# SLOPE_Undergraduate_Student_Instrumentat.net
KiCad netlist of a schematic drawn in EAGLE
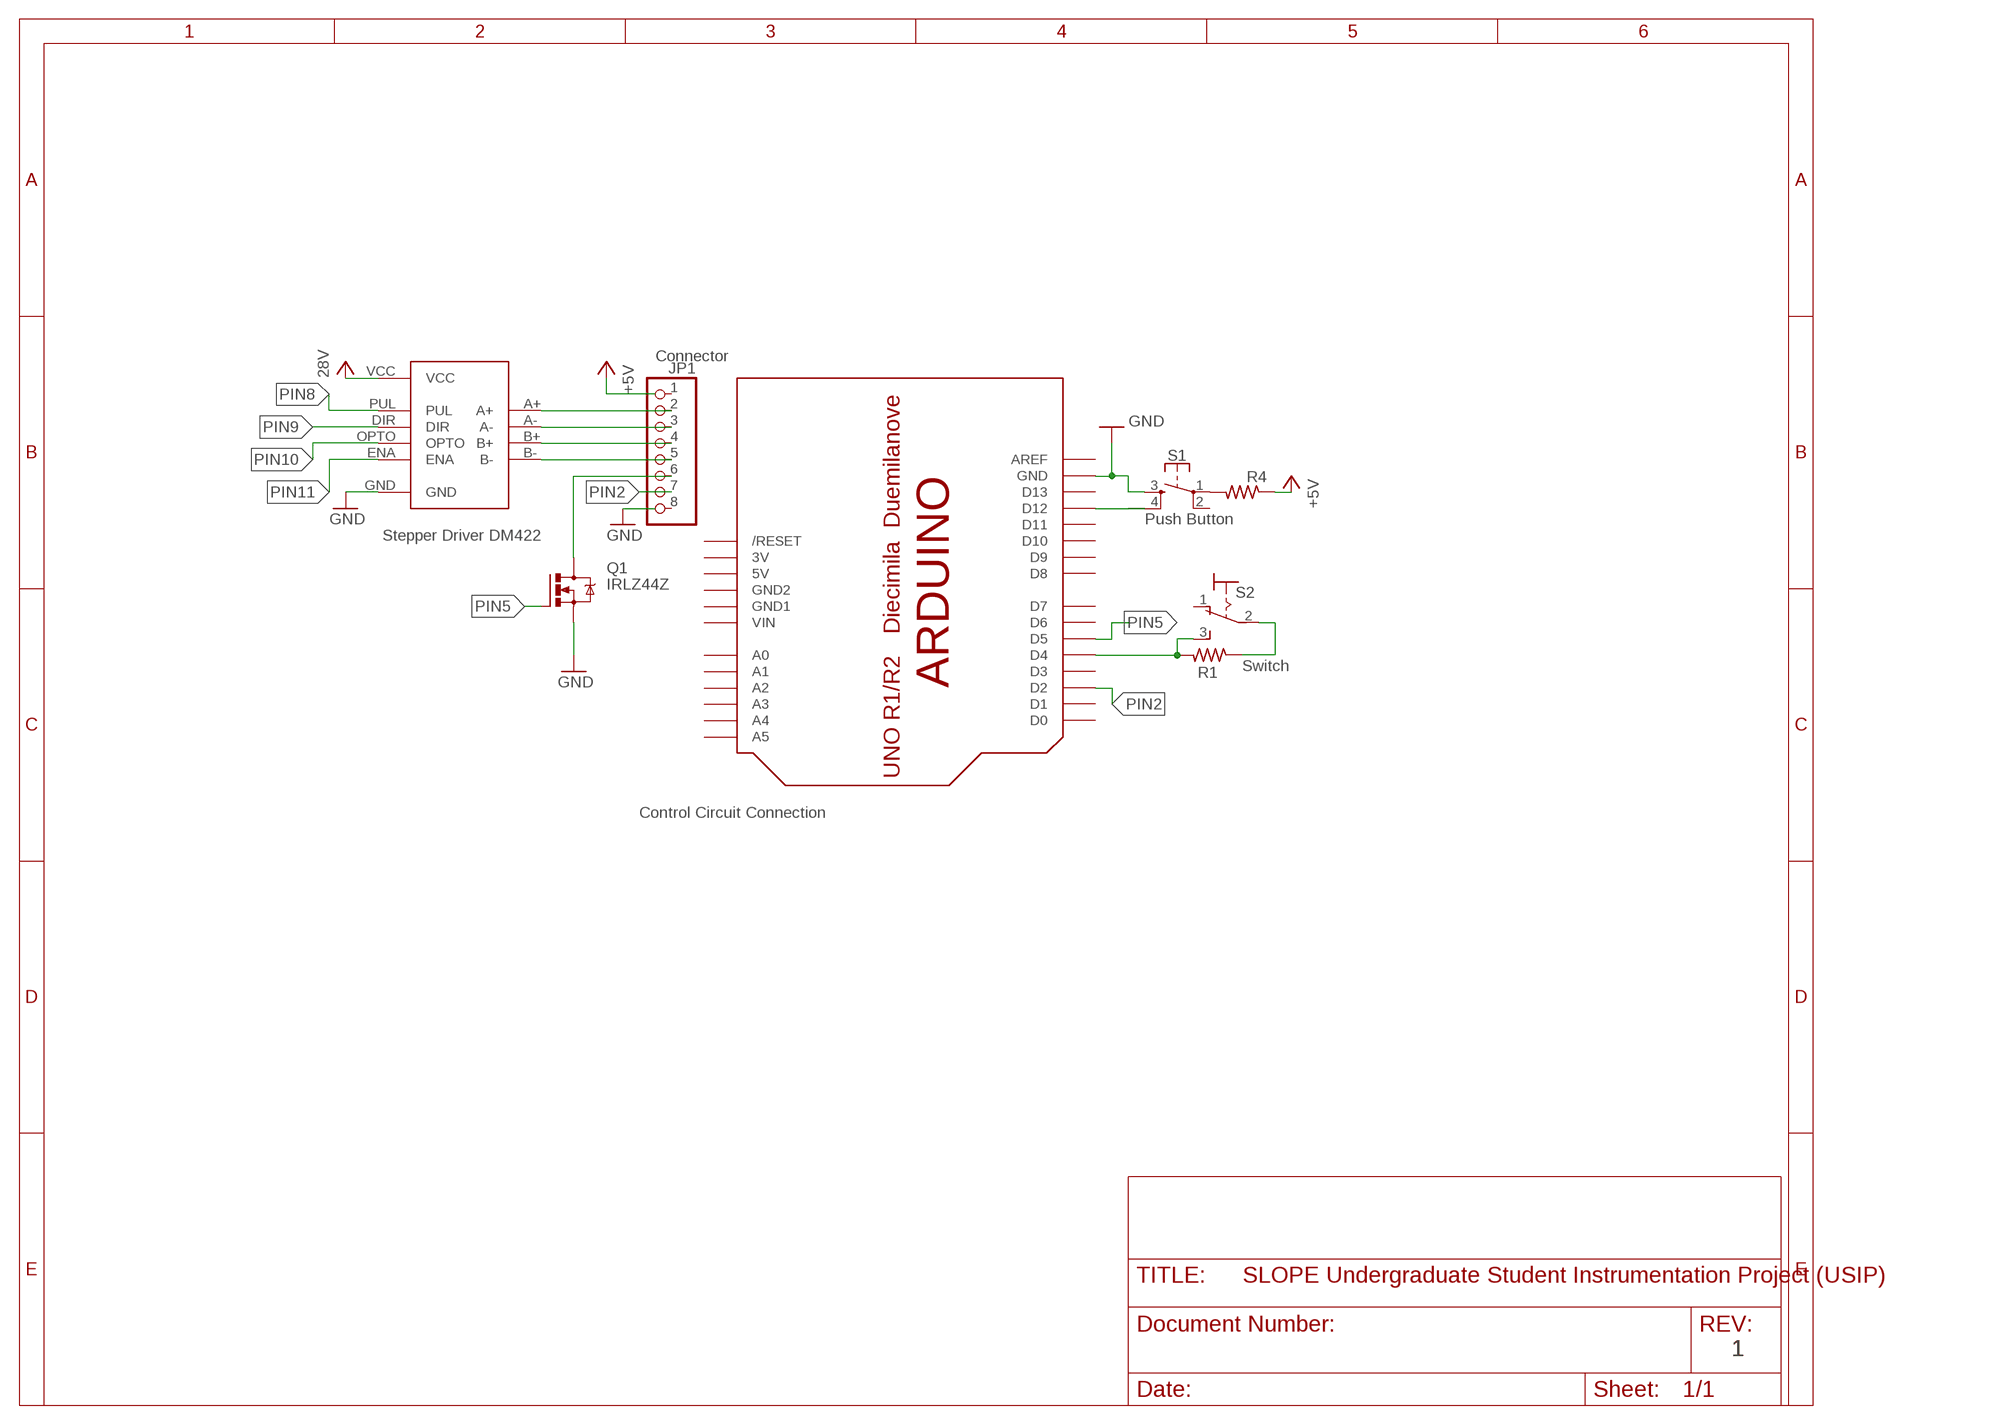
[diagram p0: schematic, sheet 1]

(export (version "E")
  (design (tool "Eeschema 10.0.6"))
  (components
    (comp (ref "JP1")
      (value "PINHD-1X8")
      (footprint "eagle-import:1X08")
      (libsource (lib "eagle-import") (part "PINHD-1X8"))
    )
    (comp (ref "Q1")
      (value "IRLZ44Z")
      (footprint "eagle-import:TO220BH")
      (libsource (lib "eagle-import") (part "IRLZ44Z"))
    )
    (comp (ref "R1")
      (value "R-US_0204/5")
      (footprint "eagle-import:0204_5")
      (libsource (lib "eagle-import") (part "R-US_0204/5"))
    )
    (comp (ref "R4")
      (value "R-US_0204/5")
      (footprint "eagle-import:0204_5")
      (libsource (lib "eagle-import") (part "R-US_0204/5"))
    )
    (comp (ref "S1")
      (value "MOMENTARY-SWITCH-SPST-2-SMD-5.2MM")
      (footprint "eagle-import:TACTILE_SWITCH_SMD_5.2MM")
      (libsource (lib "eagle-import") (part "MOMENTARY-SWITCH-SPST-2-SMD-5.2MM"))
    )
    (comp (ref "S2")
      (value "320-916")
      (footprint "eagle-import:320-916")
      (libsource (lib "eagle-import") (part "320-916"))
    )
    (comp (ref "U$1")
      (value "ARDUINO-BPLACE")
      (footprint "eagle-import:ARDUINO-BPLACE")
      (libsource (lib "eagle-import") (part "ARDUINO-BPLACE"))
    )
    (comp (ref "U$2")
      (value "DM422")
      (footprint "eagle-import:DIL14")
      (libsource (lib "eagle-import") (part "DM422"))
    )
  )
  (nets
    (net (code "1") (name "+5V") (class "Default")
      (node (ref "R4") (pin "1") (pinfunction "1_1") (pintype "passive"))
    )
    (net (code "2") (name "/3V") (class "Default")
      (node (ref "U$1") (pin "3V") (pinfunction "3V_3V") (pintype "power_in"))
    )
    (net (code "3") (name "/5V") (class "Default")
      (node (ref "U$1") (pin "5V") (pinfunction "5V_5V") (pintype "power_in"))
    )
    (net (code "4") (name "/GND1") (class "Default")
      (node (ref "U$1") (pin "GND1") (pinfunction "GND1_GND1") (pintype "power_in"))
    )
    (net (code "5") (name "/GND2") (class "Default")
      (node (ref "U$1") (pin "GND2") (pinfunction "GND2_GND2") (pintype "power_in"))
    )
    (net (code "6") (name "/VIN") (class "Default")
      (node (ref "U$1") (pin "VIN") (pinfunction "VIN_VIN") (pintype "power_in"))
    )
    (net (code "7") (name "28V") (class "Default")
      (node (ref "U$2") (pin "VCC") (pinfunction "VCC_VCC") (pintype "power_in"))
    )
    (net (code "8") (name "GND") (class "Default")
      (node (ref "Q1") (pin "S") (pinfunction "S_S") (pintype "passive"))
      (node (ref "S1") (pin "3") (pinfunction "3_3") (pintype "passive"))
      (node (ref "U$1") (pin "GND") (pinfunction "GND_GND") (pintype "power_in"))
      (node (ref "U$2") (pin "GND") (pinfunction "GND_GND") (pintype "power_in"))
    )
    (net (code "9") (name "Net-(JP1-Pad2)") (class "Default")
      (node (ref "JP1") (pin "2") (pinfunction "2_2") (pintype "passive"))
      (node (ref "U$2") (pin "A+") (pinfunction "A+_A+") (pintype "output"))
    )
    (net (code "10") (name "Net-(JP1-Pad3)") (class "Default")
      (node (ref "JP1") (pin "3") (pinfunction "3_3") (pintype "passive"))
      (node (ref "U$2") (pin "A-") (pinfunction "A-_A-") (pintype "output"))
    )
    (net (code "11") (name "Net-(JP1-Pad4)") (class "Default")
      (node (ref "JP1") (pin "4") (pinfunction "4_4") (pintype "passive"))
      (node (ref "U$2") (pin "B+") (pinfunction "B+_B+") (pintype "output"))
    )
    (net (code "12") (name "Net-(JP1-Pad5)") (class "Default")
      (node (ref "JP1") (pin "5") (pinfunction "5_5") (pintype "passive"))
      (node (ref "U$2") (pin "B-") (pinfunction "B-_B-") (pintype "output"))
    )
    (net (code "13") (name "Net-(JP1-Pad6)") (class "Default")
      (node (ref "JP1") (pin "6") (pinfunction "6_6") (pintype "passive"))
      (node (ref "Q1") (pin "D") (pinfunction "D_D") (pintype "passive"))
    )
    (net (code "14") (name "Net-(R4-Pad2)") (class "Default")
      (node (ref "R4") (pin "2") (pinfunction "2_2") (pintype "passive"))
      (node (ref "S1") (pin "1") (pinfunction "1_1") (pintype "passive"))
    )
    (net (code "15") (name "Net-(S1-Pad4)") (class "Default")
      (node (ref "S1") (pin "4") (pinfunction "4_4") (pintype "passive"))
      (node (ref "U$1") (pin "D12") (pinfunction "D12_D12") (pintype "bidirectional"))
    )
    (net (code "16") (name "Net-(S2-P)") (class "Default")
      (node (ref "R1") (pin "1") (pinfunction "1_1") (pintype "passive"))
      (node (ref "S2") (pin "2") (pinfunction "P_2") (pintype "passive"))
    )
    (net (code "17") (name "Net-(S2-S)") (class "Default")
      (node (ref "R1") (pin "2") (pinfunction "2_2") (pintype "passive"))
      (node (ref "S2") (pin "3") (pinfunction "S_3") (pintype "passive"))
      (node (ref "U$1") (pin "D4") (pinfunction "D4_D4") (pintype "bidirectional"))
    )
    (net (code "18") (name "PIN2") (class "Default")
      (node (ref "JP1") (pin "7") (pinfunction "7_7") (pintype "passive"))
      (node (ref "U$1") (pin "D2") (pinfunction "D2_D2") (pintype "bidirectional"))
    )
    (net (code "19") (name "PIN5") (class "Default")
      (node (ref "Q1") (pin "G") (pinfunction "G_G") (pintype "passive"))
      (node (ref "U$1") (pin "D5") (pinfunction "D5_D5") (pintype "bidirectional"))
    )
    (net (code "20") (name "PIN8") (class "Default")
      (node (ref "U$2") (pin "PUL") (pinfunction "PUL_PUL") (pintype "bidirectional"))
    )
    (net (code "21") (name "PIN9") (class "Default")
      (node (ref "U$2") (pin "DIR") (pinfunction "DIR_DIR") (pintype "bidirectional"))
    )
    (net (code "22") (name "PIN10") (class "Default")
      (node (ref "U$2") (pin "OPTO") (pinfunction "OPTO_OPTO") (pintype "bidirectional"))
    )
    (net (code "23") (name "PIN11") (class "Default")
      (node (ref "U$2") (pin "ENA") (pinfunction "ENA_ENA") (pintype "bidirectional"))
    )
    (net (code "24") (name "unconnected-(JP1-Pad1)") (class "Default")
      (node (ref "JP1") (pin "1") (pinfunction "1_1") (pintype "passive"))
    )
    (net (code "25") (name "unconnected-(JP1-Pad8)") (class "Default")
      (node (ref "JP1") (pin "8") (pinfunction "8_8") (pintype "passive"))
    )
    (net (code "26") (name "unconnected-(S1-Pad2)") (class "Default")
      (node (ref "S1") (pin "2") (pinfunction "2_2") (pintype "passive"))
    )
    (net (code "27") (name "unconnected-(S2-O-Pad1)") (class "Default")
      (node (ref "S2") (pin "1") (pinfunction "O_1") (pintype "passive"))
    )
    (net (code "28") (name "unconnected-(U$1-PadA0)") (class "Default")
      (node (ref "U$1") (pin "A0") (pinfunction "A0_A0") (pintype "bidirectional"))
    )
    (net (code "29") (name "unconnected-(U$1-PadA1)") (class "Default")
      (node (ref "U$1") (pin "A1") (pinfunction "A1_A1") (pintype "bidirectional"))
    )
    (net (code "30") (name "unconnected-(U$1-PadA2)") (class "Default")
      (node (ref "U$1") (pin "A2") (pinfunction "A2_A2") (pintype "bidirectional"))
    )
    (net (code "31") (name "unconnected-(U$1-PadA3)") (class "Default")
      (node (ref "U$1") (pin "A3") (pinfunction "A3_A3") (pintype "bidirectional"))
    )
    (net (code "32") (name "unconnected-(U$1-PadA4)") (class "Default")
      (node (ref "U$1") (pin "A4") (pinfunction "A4_A4") (pintype "bidirectional"))
    )
    (net (code "33") (name "unconnected-(U$1-PadA5)") (class "Default")
      (node (ref "U$1") (pin "A5") (pinfunction "A5_A5") (pintype "bidirectional"))
    )
    (net (code "34") (name "unconnected-(U$1-PadAREF)") (class "Default")
      (node (ref "U$1") (pin "AREF") (pinfunction "AREF_AREF") (pintype "bidirectional"))
    )
    (net (code "35") (name "unconnected-(U$1-PadD0)") (class "Default")
      (node (ref "U$1") (pin "D0") (pinfunction "D0_D0") (pintype "bidirectional"))
    )
    (net (code "36") (name "unconnected-(U$1-PadD1)") (class "Default")
      (node (ref "U$1") (pin "D1") (pinfunction "D1_D1") (pintype "bidirectional"))
    )
    (net (code "37") (name "unconnected-(U$1-PadD3)") (class "Default")
      (node (ref "U$1") (pin "D3") (pinfunction "D3_D3") (pintype "bidirectional"))
    )
    (net (code "38") (name "unconnected-(U$1-PadD6)") (class "Default")
      (node (ref "U$1") (pin "D6") (pinfunction "D6_D6") (pintype "bidirectional"))
    )
    (net (code "39") (name "unconnected-(U$1-PadD7)") (class "Default")
      (node (ref "U$1") (pin "D7") (pinfunction "D7_D7") (pintype "bidirectional"))
    )
    (net (code "40") (name "unconnected-(U$1-PadD8)") (class "Default")
      (node (ref "U$1") (pin "D8") (pinfunction "D8_D8") (pintype "bidirectional"))
    )
    (net (code "41") (name "unconnected-(U$1-PadD9)") (class "Default")
      (node (ref "U$1") (pin "D9") (pinfunction "D9_D9") (pintype "bidirectional"))
    )
    (net (code "42") (name "unconnected-(U$1-PadD10)") (class "Default")
      (node (ref "U$1") (pin "D10") (pinfunction "D10_D10") (pintype "bidirectional"))
    )
    (net (code "43") (name "unconnected-(U$1-PadD11)") (class "Default")
      (node (ref "U$1") (pin "D11") (pinfunction "D11_D11") (pintype "bidirectional"))
    )
    (net (code "44") (name "unconnected-(U$1-PadD13)") (class "Default")
      (node (ref "U$1") (pin "D13") (pinfunction "D13_D13") (pintype "bidirectional"))
    )
    (net (code "45") (name "unconnected-(U$1-{slash}RESET-PadRESET)") (class "Default")
      (node (ref "U$1") (pin "RESET") (pinfunction "/RESET_RESET") (pintype "bidirectional"))
    )
  )
)
